# 24VCC_GNDPort.net
KiCad netlist of a schematic drawn in Altium Designer
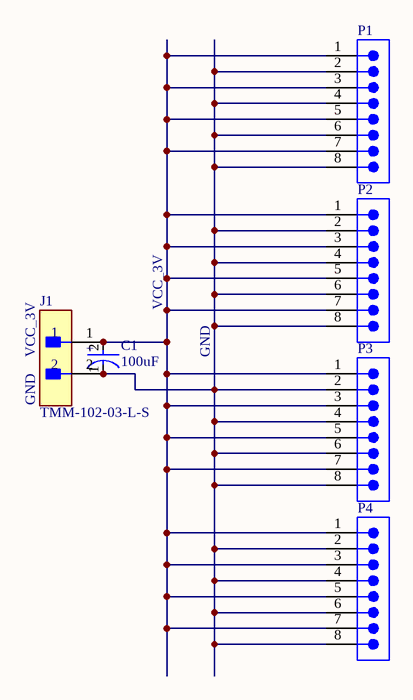
[diagram p0: 24VCC_GNDPort.SchDoc]

(export (version "E")
  (design (tool "Eeschema 10.0.6"))
  (components
    (comp (ref "C1")
      (value "100uF")
      (footprint "FP-RAD-TH-D_6_3_0_5-L_11-MFG")
      (description "Aluminum Electrolytic Capacitors (Radial Lead Type) 100uF ±20% 25V")
      (fields (field (name "TOLERANCE") "20%"))
      (libsource (lib "Altium Content Vault") (part "a00bbbee19879c290e62620ae7e47b1"))
    )
    (comp (ref "J1")
      (value "TMM-102-03-L-S")
      (footprint "FP-TMM-102-03-L-S-MFG")
      (description "CONN HEADER 2POS SNGL 2MM T/H")
      (libsource (lib "Altium Content Vault") (part "3bc925449376181038e59eaffc5286c"))
    )
    (comp (ref "P1")
      (value "~")
      (footprint "62000811722")
      (description "WR-WTB Wire-to-Board Connectors 2.00 mm")
      (libsource (lib "Altium Content Vault") (part "Header_Male_1R_08P"))
    )
    (comp (ref "P2")
      (value "~")
      (footprint "62000811722")
      (description "WR-WTB Wire-to-Board Connectors 2.00 mm")
      (libsource (lib "Altium Content Vault") (part "Header_Male_1R_08P"))
    )
    (comp (ref "P3")
      (value "~")
      (footprint "62000811722")
      (description "WR-WTB Wire-to-Board Connectors 2.00 mm")
      (libsource (lib "Altium Content Vault") (part "Header_Male_1R_08P"))
    )
    (comp (ref "P4")
      (value "~")
      (footprint "62000811722")
      (description "WR-WTB Wire-to-Board Connectors 2.00 mm")
      (libsource (lib "Altium Content Vault") (part "Header_Male_1R_08P"))
    )
  )
  (nets
    (net (code "1") (name "Net-(C1-A)") (class "Default")
      (node (ref "C1") (pin "2") (pinfunction "A_2") (pintype "passive"))
      (node (ref "J1") (pin "1") (pinfunction "1_1") (pintype "passive"))
      (node (ref "P1") (pin "1") (pinfunction "1_1") (pintype "passive"))
      (node (ref "P1") (pin "3") (pinfunction "3_3") (pintype "passive"))
      (node (ref "P1") (pin "5") (pinfunction "5_5") (pintype "passive"))
      (node (ref "P1") (pin "7") (pinfunction "7_7") (pintype "passive"))
      (node (ref "P2") (pin "1") (pinfunction "1_1") (pintype "passive"))
      (node (ref "P2") (pin "3") (pinfunction "3_3") (pintype "passive"))
      (node (ref "P2") (pin "5") (pinfunction "5_5") (pintype "passive"))
      (node (ref "P2") (pin "7") (pinfunction "7_7") (pintype "passive"))
      (node (ref "P3") (pin "1") (pinfunction "1_1") (pintype "passive"))
      (node (ref "P3") (pin "3") (pinfunction "3_3") (pintype "passive"))
      (node (ref "P3") (pin "5") (pinfunction "5_5") (pintype "passive"))
      (node (ref "P3") (pin "7") (pinfunction "7_7") (pintype "passive"))
      (node (ref "P4") (pin "1") (pinfunction "1_1") (pintype "passive"))
      (node (ref "P4") (pin "3") (pinfunction "3_3") (pintype "passive"))
      (node (ref "P4") (pin "5") (pinfunction "5_5") (pintype "passive"))
      (node (ref "P4") (pin "7") (pinfunction "7_7") (pintype "passive"))
    )
    (net (code "2") (name "Net-(C1-C)") (class "Default")
      (node (ref "C1") (pin "1") (pinfunction "C_1") (pintype "passive"))
      (node (ref "J1") (pin "2") (pinfunction "2_2") (pintype "passive"))
      (node (ref "P1") (pin "2") (pinfunction "2_2") (pintype "passive"))
      (node (ref "P1") (pin "4") (pinfunction "4_4") (pintype "passive"))
      (node (ref "P1") (pin "6") (pinfunction "6_6") (pintype "passive"))
      (node (ref "P1") (pin "8") (pinfunction "8_8") (pintype "passive"))
      (node (ref "P2") (pin "2") (pinfunction "2_2") (pintype "passive"))
      (node (ref "P2") (pin "4") (pinfunction "4_4") (pintype "passive"))
      (node (ref "P2") (pin "6") (pinfunction "6_6") (pintype "passive"))
      (node (ref "P2") (pin "8") (pinfunction "8_8") (pintype "passive"))
      (node (ref "P3") (pin "2") (pinfunction "2_2") (pintype "passive"))
      (node (ref "P3") (pin "4") (pinfunction "4_4") (pintype "passive"))
      (node (ref "P3") (pin "6") (pinfunction "6_6") (pintype "passive"))
      (node (ref "P3") (pin "8") (pinfunction "8_8") (pintype "passive"))
      (node (ref "P4") (pin "2") (pinfunction "2_2") (pintype "passive"))
      (node (ref "P4") (pin "4") (pinfunction "4_4") (pintype "passive"))
      (node (ref "P4") (pin "6") (pinfunction "6_6") (pintype "passive"))
      (node (ref "P4") (pin "8") (pinfunction "8_8") (pintype "passive"))
    )
  )
)
